# PMW3360MouseSensor.net
KiCad netlist of a schematic drawn in EAGLE
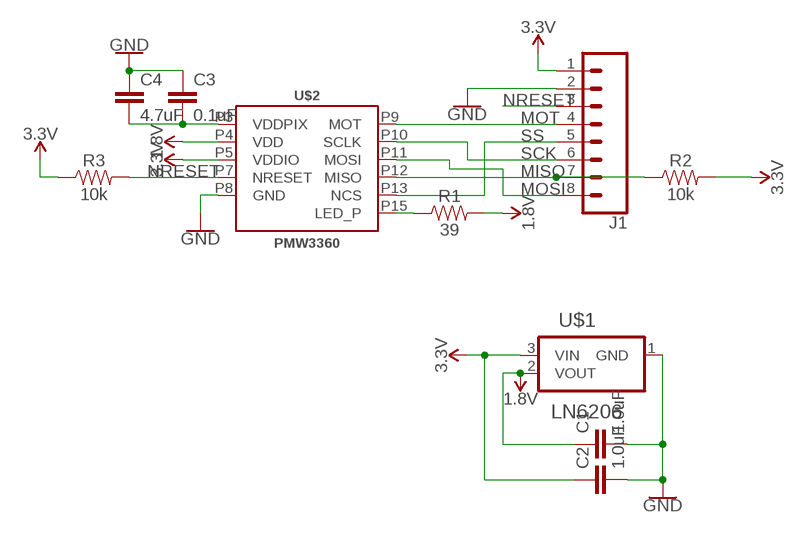
[diagram p0: schematic, sheet 1]

(export (version "E")
  (design (tool "Eeschema 10.0.6"))
  (components
    (comp (ref "C1")
      (value "1.0uF")
      (footprint "eagle-import:0603")
      (libsource (lib "eagle-import") (part "1.0UF-0603-16V-10%-X7R"))
    )
    (comp (ref "C2")
      (value "1.0uF")
      (footprint "eagle-import:0603")
      (libsource (lib "eagle-import") (part "1.0UF-0603-16V-10%-X7R"))
    )
    (comp (ref "C3")
      (value "0.1uF")
      (footprint "eagle-import:0603")
      (libsource (lib "eagle-import") (part "0.1UF-0603-25V-5%"))
    )
    (comp (ref "C4")
      (value "4.7uF")
      (footprint "eagle-import:0603")
      (libsource (lib "eagle-import") (part "4.7UF-0603-6.3V-(10%)"))
    )
    (comp (ref "J1")
      (value "CONN_08LOCK")
      (footprint "eagle-import:1X08_LOCK")
      (libsource (lib "eagle-import") (part "CONN_08LOCK"))
    )
    (comp (ref "R1")
      (value "39")
      (footprint "eagle-import:0603")
      (libsource (lib "eagle-import") (part "RESISTOR0603"))
    )
    (comp (ref "R2")
      (value "10k")
      (footprint "eagle-import:0603")
      (libsource (lib "eagle-import") (part "10KOHM-0603-1/10W-1%"))
    )
    (comp (ref "R3")
      (value "10k")
      (footprint "eagle-import:0603")
      (libsource (lib "eagle-import") (part "10KOHM-0603-1/10W-1%"))
    )
    (comp (ref "U$1")
      (value "LN6206")
      (footprint "eagle-import:SOT95P237X112-3N")
      (fields (field (name "MF") "Microchip") (field (name "MP") "MCP1700T-3302E/TT"))
      (libsource (lib "eagle-import") (part "MCP1700T-3302E/TT"))
    )
    (comp (ref "U$2")
      (value "PMW3360")
      (footprint "eagle-import:PMW3360")
      (libsource (lib "eagle-import") (part "PMW3360"))
    )
  )
  (nets
    (net (code "1") (name "/MISO") (class "Default")
      (node (ref "J1") (pin "7") (pinfunction "7_7") (pintype "passive"))
      (node (ref "R2") (pin "1") (pinfunction "1_1") (pintype "passive"))
      (node (ref "U$2") (pin "P12") (pinfunction "MISO_P12") (pintype "output"))
    )
    (net (code "2") (name "/MOSI") (class "Default")
      (node (ref "J1") (pin "8") (pinfunction "8_8") (pintype "passive"))
      (node (ref "U$2") (pin "P11") (pinfunction "MOSI_P11") (pintype "input"))
    )
    (net (code "3") (name "/MOT") (class "Default")
      (node (ref "J1") (pin "4") (pinfunction "4_4") (pintype "passive"))
      (node (ref "U$2") (pin "P9") (pinfunction "MOT_P9") (pintype "output"))
    )
    (net (code "4") (name "/NRESET") (class "Default")
      (node (ref "J1") (pin "3") (pinfunction "3_3") (pintype "passive"))
      (node (ref "R3") (pin "2") (pinfunction "2_2") (pintype "passive"))
      (node (ref "U$2") (pin "P7") (pinfunction "NRESET_P7") (pintype "input"))
    )
    (net (code "5") (name "/SCK") (class "Default")
      (node (ref "J1") (pin "6") (pinfunction "6_6") (pintype "passive"))
      (node (ref "U$2") (pin "P10") (pinfunction "SCLK_P10") (pintype "input"))
    )
    (net (code "6") (name "/SS") (class "Default")
      (node (ref "J1") (pin "5") (pinfunction "5_5") (pintype "passive"))
      (node (ref "U$2") (pin "P13") (pinfunction "NCS_P13") (pintype "input"))
    )
    (net (code "7") (name "1.8V") (class "Default")
      (node (ref "C1") (pin "1") (pinfunction "1_1") (pintype "passive"))
      (node (ref "R1") (pin "2") (pinfunction "2_2") (pintype "passive"))
      (node (ref "U$1") (pin "2") (pinfunction "VOUT_2") (pintype "output"))
      (node (ref "U$2") (pin "P4") (pinfunction "VDD_P4") (pintype "power_in"))
    )
    (net (code "8") (name "3.3V") (class "Default")
      (node (ref "C2") (pin "1") (pinfunction "1_1") (pintype "passive"))
      (node (ref "J1") (pin "1") (pinfunction "1_1") (pintype "passive"))
      (node (ref "R2") (pin "2") (pinfunction "2_2") (pintype "passive"))
      (node (ref "R3") (pin "1") (pinfunction "1_1") (pintype "passive"))
      (node (ref "U$1") (pin "3") (pinfunction "VIN_3") (pintype "input"))
      (node (ref "U$2") (pin "P5") (pinfunction "VDDIO_P5") (pintype "power_in"))
    )
    (net (code "9") (name "GND") (class "Default")
      (node (ref "C1") (pin "2") (pinfunction "2_2") (pintype "passive"))
      (node (ref "C2") (pin "2") (pinfunction "2_2") (pintype "passive"))
      (node (ref "C3") (pin "1") (pinfunction "1_1") (pintype "passive"))
      (node (ref "C4") (pin "1") (pinfunction "1_1") (pintype "passive"))
      (node (ref "J1") (pin "2") (pinfunction "2_2") (pintype "passive"))
      (node (ref "U$1") (pin "1") (pinfunction "GND_1") (pintype "power_in"))
      (node (ref "U$2") (pin "P8") (pinfunction "GND_P8") (pintype "power_in"))
    )
    (net (code "10") (name "Net-(U$2-LED_P)") (class "Default")
      (node (ref "R1") (pin "1") (pinfunction "1_1") (pintype "passive"))
      (node (ref "U$2") (pin "P15") (pinfunction "LED_P_P15") (pintype "input"))
    )
    (net (code "11") (name "Net-(U$2-VDDPIX)") (class "Default")
      (node (ref "C3") (pin "2") (pinfunction "2_2") (pintype "passive"))
      (node (ref "C4") (pin "2") (pinfunction "2_2") (pintype "passive"))
      (node (ref "U$2") (pin "P3") (pinfunction "VDDPIX_P3") (pintype "power_in"))
    )
    (net (code "12") (name "unconnected-(U$2-P$1-PadP1)") (class "Default")
      (node (ref "U$2") (pin "P1") (pinfunction "P$1_P1") (pintype "no_connect"))
    )
    (net (code "13") (name "unconnected-(U$2-P$1-PadP2)") (class "Default")
      (node (ref "U$2") (pin "P2") (pinfunction "P$1_P2") (pintype "no_connect"))
    )
    (net (code "14") (name "unconnected-(U$2-P$1-PadP6)") (class "Default")
      (node (ref "U$2") (pin "P6") (pinfunction "P$1_P6") (pintype "no_connect"))
    )
    (net (code "15") (name "unconnected-(U$2-P$1-PadP14)") (class "Default")
      (node (ref "U$2") (pin "P14") (pinfunction "P$1_P14") (pintype "no_connect"))
    )
    (net (code "16") (name "unconnected-(U$2-P$1-PadP16)") (class "Default")
      (node (ref "U$2") (pin "P16") (pinfunction "P$1_P16") (pintype "no_connect"))
    )
  )
)
